# sci_fair_schematic.net
KiCad netlist of a schematic drawn in EAGLE
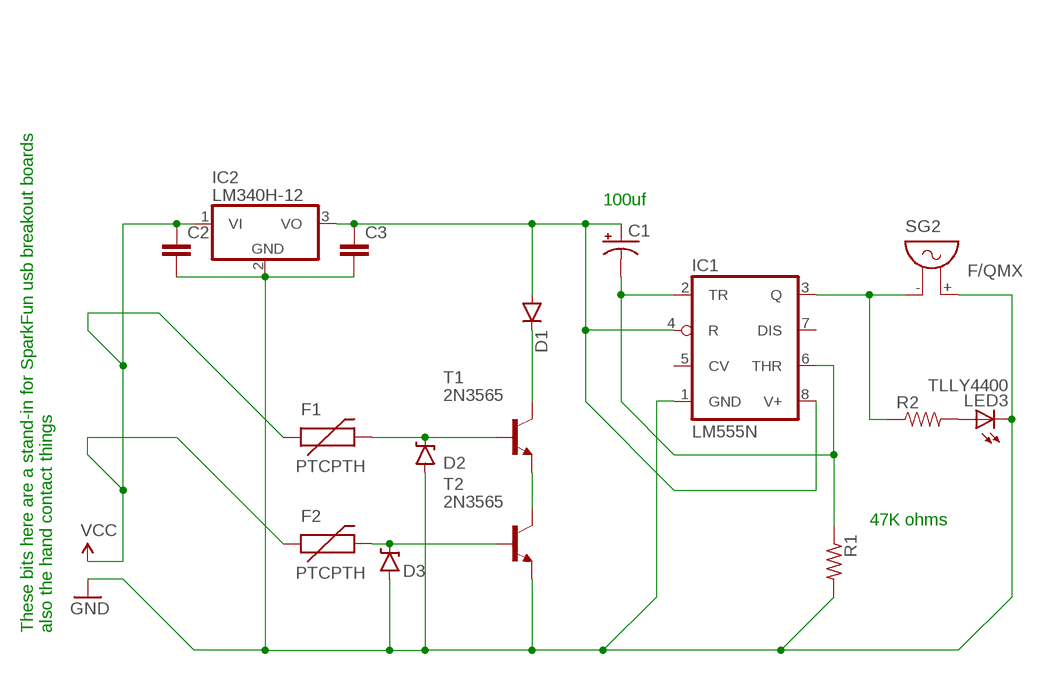
[diagram p0: schematic, sheet 1]

(export (version "E")
  (design (tool "Eeschema 10.0.6"))
  (components
    (comp (ref "C1")
      (value "CAP_POLPTH1")
      (footprint "eagle-import:CPOL-RADIAL-100UF-25V")
      (libsource (lib "eagle-import") (part "CAP_POLPTH1"))
    )
    (comp (ref "C2")
      (value "C5/2.5")
      (footprint "eagle-import:C5B2.5")
      (libsource (lib "eagle-import") (part "C5/2.5"))
    )
    (comp (ref "C3")
      (value "C5/2.5")
      (footprint "eagle-import:C5B2.5")
      (libsource (lib "eagle-import") (part "C5/2.5"))
    )
    (comp (ref "D1")
      (value "DIODEPTH")
      (footprint "eagle-import:DIODE-1N4001")
      (libsource (lib "eagle-import") (part "DIODEPTH"))
    )
    (comp (ref "D2")
      (value "DIODE-ZENERPTH")
      (footprint "eagle-import:DIODE-ZENER")
      (libsource (lib "eagle-import") (part "DIODE-ZENERPTH"))
    )
    (comp (ref "D3")
      (value "DIODE-ZENERPTH")
      (footprint "eagle-import:DIODE-ZENER")
      (libsource (lib "eagle-import") (part "DIODE-ZENERPTH"))
    )
    (comp (ref "F1")
      (value "PTCPTH")
      (footprint "eagle-import:PTC")
      (libsource (lib "eagle-import") (part "PTCPTH"))
    )
    (comp (ref "F2")
      (value "PTCPTH")
      (footprint "eagle-import:PTC")
      (libsource (lib "eagle-import") (part "PTCPTH"))
    )
    (comp (ref "IC1")
      (value "LM555N")
      (footprint "eagle-import:DIL08")
      (libsource (lib "eagle-import") (part "555NLM"))
    )
    (comp (ref "IC2")
      (value "LM340H-12")
      (footprint "eagle-import:TO220H")
      (libsource (lib "eagle-import") (part "LM340?-H12"))
    )
    (comp (ref "LED3")
      (value "TLLY4400")
      (footprint "eagle-import:LED3MM")
      (fields (field (name "MF") "VISHAY SEMICONDUCTOR"))
      (libsource (lib "eagle-import") (part "TLLY4400"))
    )
    (comp (ref "R1")
      (value "R-US_0207/12")
      (footprint "eagle-import:0207_12")
      (libsource (lib "eagle-import") (part "R-US_0207/12"))
    )
    (comp (ref "R2")
      (value "RESISTORPTH-1/2W")
      (footprint "eagle-import:AXIAL-0.5")
      (libsource (lib "eagle-import") (part "RESISTORPTH-1/2W"))
    )
    (comp (ref "SG2")
      (value "F/QMX")
      (footprint "eagle-import:F_QMX")
      (libsource (lib "eagle-import") (part "F/QMX"))
    )
    (comp (ref "T1")
      (value "2N3565")
      (footprint "eagle-import:TO92")
      (libsource (lib "eagle-import") (part "2N3565"))
    )
    (comp (ref "T2")
      (value "2N3565")
      (footprint "eagle-import:TO92")
      (libsource (lib "eagle-import") (part "2N3565"))
    )
  )
  (nets
    (net (code "1") (name "GND") (class "Default")
      (node (ref "C2") (pin "2") (pinfunction "2_2") (pintype "passive"))
      (node (ref "C3") (pin "2") (pinfunction "2_2") (pintype "passive"))
      (node (ref "D2") (pin "P$2") (pinfunction "A_P$2") (pintype "passive"))
      (node (ref "D3") (pin "P$2") (pinfunction "A_P$2") (pintype "passive"))
      (node (ref "IC1") (pin "1") (pinfunction "GND_1") (pintype "power_in"))
      (node (ref "IC2") (pin "2") (pinfunction "GND_2") (pintype "passive"))
      (node (ref "LED3") (pin "K") (pinfunction "C_K") (pintype "passive"))
      (node (ref "R1") (pin "2") (pinfunction "2_2") (pintype "passive"))
      (node (ref "SG2") (pin "+") (pinfunction "2_+") (pintype "passive"))
      (node (ref "T2") (pin "3") (pinfunction "E_3") (pintype "passive"))
    )
    (net (code "2") (name "Net-(C1-+)") (class "Default")
      (node (ref "C1") (pin "1") (pinfunction "+_1") (pintype "passive"))
      (node (ref "C3") (pin "1") (pinfunction "1_1") (pintype "passive"))
      (node (ref "D1") (pin "A") (pinfunction "A_A") (pintype "passive"))
      (node (ref "IC1") (pin "4") (pinfunction "R_4") (pintype "input"))
      (node (ref "IC1") (pin "8") (pinfunction "V+_8") (pintype "power_in"))
      (node (ref "IC2") (pin "3") (pinfunction "VO_3") (pintype "passive"))
    )
    (net (code "3") (name "Net-(C1--)") (class "Default")
      (node (ref "C1") (pin "2") (pinfunction "-_2") (pintype "passive"))
      (node (ref "IC1") (pin "2") (pinfunction "TR_2") (pintype "input"))
      (node (ref "IC1") (pin "6") (pinfunction "THR_6") (pintype "input"))
      (node (ref "R1") (pin "1") (pinfunction "1_1") (pintype "passive"))
    )
    (net (code "4") (name "Net-(D2-C)") (class "Default")
      (node (ref "D2") (pin "P$1") (pinfunction "C_P$1") (pintype "passive"))
      (node (ref "F1") (pin "P$2") (pinfunction "2_P$2") (pintype "bidirectional"))
      (node (ref "T1") (pin "2") (pinfunction "B_2") (pintype "passive"))
    )
    (net (code "5") (name "Net-(D3-C)") (class "Default")
      (node (ref "D3") (pin "P$1") (pinfunction "C_P$1") (pintype "passive"))
      (node (ref "F2") (pin "P$2") (pinfunction "2_P$2") (pintype "bidirectional"))
      (node (ref "T2") (pin "2") (pinfunction "B_2") (pintype "passive"))
    )
    (net (code "6") (name "Net-(IC1-Q)") (class "Default")
      (node (ref "IC1") (pin "3") (pinfunction "Q_3") (pintype "output"))
      (node (ref "R2") (pin "P$1") (pinfunction "1_P$1") (pintype "passive"))
      (node (ref "SG2") (pin "-") (pinfunction "1_-") (pintype "passive"))
    )
    (net (code "7") (name "Net-(R2-2)") (class "Default")
      (node (ref "LED3") (pin "A") (pinfunction "A_A") (pintype "passive"))
      (node (ref "R2") (pin "P$2") (pinfunction "2_P$2") (pintype "passive"))
    )
    (net (code "8") (name "Net-(T1-C)") (class "Default")
      (node (ref "D1") (pin "C") (pinfunction "C_C") (pintype "passive"))
      (node (ref "T1") (pin "1") (pinfunction "C_1") (pintype "passive"))
    )
    (net (code "9") (name "Net-(T1-E)") (class "Default")
      (node (ref "T1") (pin "3") (pinfunction "E_3") (pintype "passive"))
      (node (ref "T2") (pin "1") (pinfunction "C_1") (pintype "passive"))
    )
    (net (code "10") (name "VCC") (class "Default")
      (node (ref "C2") (pin "1") (pinfunction "1_1") (pintype "passive"))
      (node (ref "F1") (pin "P$1") (pinfunction "1_P$1") (pintype "bidirectional"))
      (node (ref "F2") (pin "P$1") (pinfunction "1_P$1") (pintype "bidirectional"))
      (node (ref "IC2") (pin "1") (pinfunction "VI_1") (pintype "input"))
    )
    (net (code "11") (name "unconnected-(IC1-CV-Pad5)") (class "Default")
      (node (ref "IC1") (pin "5") (pinfunction "CV_5") (pintype "input"))
    )
    (net (code "12") (name "unconnected-(IC1-DIS-Pad7)") (class "Default")
      (node (ref "IC1") (pin "7") (pinfunction "DIS_7") (pintype "input"))
    )
  )
)
